# jam2.net
KiCad netlist of a schematic drawn in EAGLE
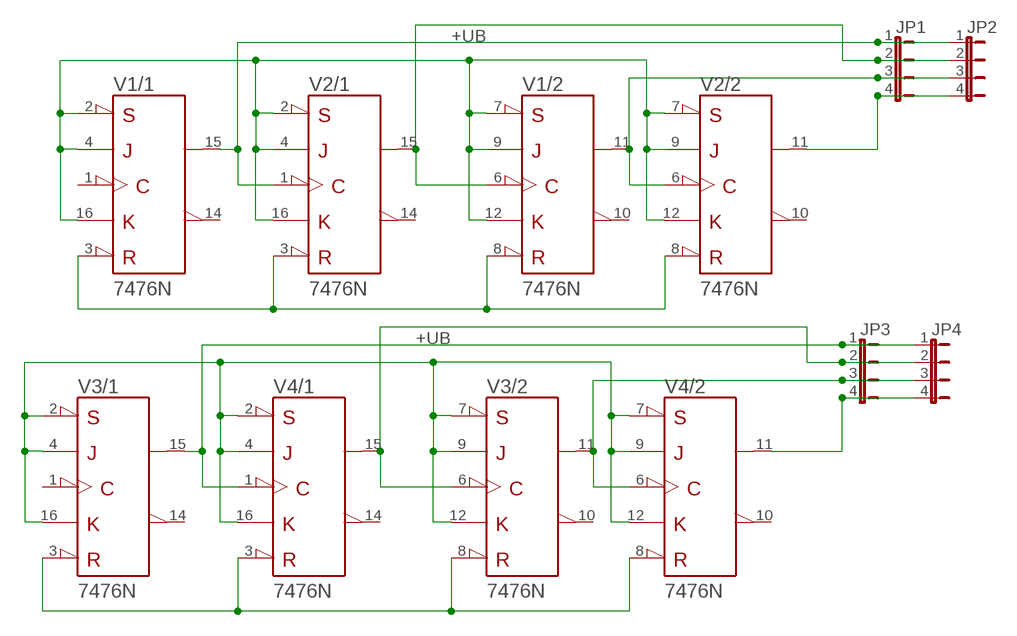
[diagram p0: schematic, sheet 1]

(export (version "E")
  (design (tool "Eeschema 10.0.6"))
  (components
    (comp (ref "JP1")
      (value "JP4E")
      (footprint "eagle-import:JP4")
      (libsource (lib "eagle-import") (part "JP4E"))
    )
    (comp (ref "JP2")
      (value "JP4E")
      (footprint "eagle-import:JP4")
      (libsource (lib "eagle-import") (part "JP4E"))
    )
    (comp (ref "JP3")
      (value "JP4E")
      (footprint "eagle-import:JP4")
      (libsource (lib "eagle-import") (part "JP4E"))
    )
    (comp (ref "JP4")
      (value "JP4E")
      (footprint "eagle-import:JP4")
      (libsource (lib "eagle-import") (part "JP4E"))
    )
    (comp (ref "V1")
      (value "7476N")
      (footprint "eagle-import:DIL16")
      (libsource (lib "eagle-import") (part "7476N"))
    )
    (comp (ref "V2")
      (value "7476N")
      (footprint "eagle-import:DIL16")
      (libsource (lib "eagle-import") (part "7476N"))
    )
    (comp (ref "V3")
      (value "7476N")
      (footprint "eagle-import:DIL16")
      (libsource (lib "eagle-import") (part "7476N"))
    )
    (comp (ref "V4")
      (value "7476N")
      (footprint "eagle-import:DIL16")
      (libsource (lib "eagle-import") (part "7476N"))
    )
  )
  (nets
    (net (code "1") (name "/+UB") (class "Default")
      (node (ref "V1") (pin "12") (pinfunction "K_12") (pintype "input"))
      (node (ref "V1") (pin "16") (pinfunction "K_16") (pintype "input"))
      (node (ref "V1") (pin "2") (pinfunction "~{PRE}_2") (pintype "input"))
      (node (ref "V1") (pin "4") (pinfunction "J_4") (pintype "input"))
      (node (ref "V1") (pin "7") (pinfunction "~{PRE}_7") (pintype "input"))
      (node (ref "V1") (pin "9") (pinfunction "J_9") (pintype "input"))
      (node (ref "V2") (pin "12") (pinfunction "K_12") (pintype "input"))
      (node (ref "V2") (pin "16") (pinfunction "K_16") (pintype "input"))
      (node (ref "V2") (pin "2") (pinfunction "~{PRE}_2") (pintype "input"))
      (node (ref "V2") (pin "4") (pinfunction "J_4") (pintype "input"))
      (node (ref "V2") (pin "7") (pinfunction "~{PRE}_7") (pintype "input"))
      (node (ref "V2") (pin "9") (pinfunction "J_9") (pintype "input"))
      (node (ref "V3") (pin "12") (pinfunction "K_12") (pintype "input"))
      (node (ref "V3") (pin "16") (pinfunction "K_16") (pintype "input"))
      (node (ref "V3") (pin "2") (pinfunction "~{PRE}_2") (pintype "input"))
      (node (ref "V3") (pin "4") (pinfunction "J_4") (pintype "input"))
      (node (ref "V3") (pin "7") (pinfunction "~{PRE}_7") (pintype "input"))
      (node (ref "V3") (pin "9") (pinfunction "J_9") (pintype "input"))
      (node (ref "V4") (pin "12") (pinfunction "K_12") (pintype "input"))
      (node (ref "V4") (pin "16") (pinfunction "K_16") (pintype "input"))
      (node (ref "V4") (pin "2") (pinfunction "~{PRE}_2") (pintype "input"))
      (node (ref "V4") (pin "4") (pinfunction "J_4") (pintype "input"))
      (node (ref "V4") (pin "7") (pinfunction "~{PRE}_7") (pintype "input"))
      (node (ref "V4") (pin "9") (pinfunction "J_9") (pintype "input"))
    )
    (net (code "2") (name "Net-(V1C-Q)") (class "Default")
      (node (ref "JP1") (pin "1") (pinfunction "1_1") (pintype "passive"))
      (node (ref "JP2") (pin "1") (pinfunction "1_1") (pintype "passive"))
      (node (ref "V1") (pin "15") (pinfunction "Q_15") (pintype "output"))
      (node (ref "V2") (pin "1") (pinfunction "CLK_1") (pintype "input"))
    )
    (net (code "3") (name "Net-(V1C-~{CLR})") (class "Default")
      (node (ref "V1") (pin "3") (pinfunction "~{CLR}_3") (pintype "input"))
      (node (ref "V1") (pin "8") (pinfunction "~{CLR}_8") (pintype "input"))
      (node (ref "V2") (pin "3") (pinfunction "~{CLR}_3") (pintype "input"))
      (node (ref "V2") (pin "8") (pinfunction "~{CLR}_8") (pintype "input"))
    )
    (net (code "4") (name "Net-(V1D-CLK)") (class "Default")
      (node (ref "JP1") (pin "2") (pinfunction "2_2") (pintype "passive"))
      (node (ref "JP2") (pin "2") (pinfunction "2_2") (pintype "passive"))
      (node (ref "V1") (pin "6") (pinfunction "CLK_6") (pintype "input"))
      (node (ref "V2") (pin "15") (pinfunction "Q_15") (pintype "output"))
    )
    (net (code "5") (name "Net-(V1D-Q)") (class "Default")
      (node (ref "JP1") (pin "3") (pinfunction "3_3") (pintype "passive"))
      (node (ref "JP2") (pin "3") (pinfunction "3_3") (pintype "passive"))
      (node (ref "V1") (pin "11") (pinfunction "Q_11") (pintype "output"))
      (node (ref "V2") (pin "6") (pinfunction "CLK_6") (pintype "input"))
    )
    (net (code "6") (name "Net-(V2D-Q)") (class "Default")
      (node (ref "JP1") (pin "4") (pinfunction "4_4") (pintype "passive"))
      (node (ref "JP2") (pin "4") (pinfunction "4_4") (pintype "passive"))
      (node (ref "V2") (pin "11") (pinfunction "Q_11") (pintype "output"))
    )
    (net (code "7") (name "Net-(V3C-Q)") (class "Default")
      (node (ref "JP3") (pin "1") (pinfunction "1_1") (pintype "passive"))
      (node (ref "JP4") (pin "1") (pinfunction "1_1") (pintype "passive"))
      (node (ref "V3") (pin "15") (pinfunction "Q_15") (pintype "output"))
      (node (ref "V4") (pin "1") (pinfunction "CLK_1") (pintype "input"))
    )
    (net (code "8") (name "Net-(V3C-~{CLR})") (class "Default")
      (node (ref "V3") (pin "3") (pinfunction "~{CLR}_3") (pintype "input"))
      (node (ref "V3") (pin "8") (pinfunction "~{CLR}_8") (pintype "input"))
      (node (ref "V4") (pin "3") (pinfunction "~{CLR}_3") (pintype "input"))
      (node (ref "V4") (pin "8") (pinfunction "~{CLR}_8") (pintype "input"))
    )
    (net (code "9") (name "Net-(V3D-CLK)") (class "Default")
      (node (ref "JP3") (pin "2") (pinfunction "2_2") (pintype "passive"))
      (node (ref "JP4") (pin "2") (pinfunction "2_2") (pintype "passive"))
      (node (ref "V3") (pin "6") (pinfunction "CLK_6") (pintype "input"))
      (node (ref "V4") (pin "15") (pinfunction "Q_15") (pintype "output"))
    )
    (net (code "10") (name "Net-(V3D-Q)") (class "Default")
      (node (ref "JP3") (pin "3") (pinfunction "3_3") (pintype "passive"))
      (node (ref "JP4") (pin "3") (pinfunction "3_3") (pintype "passive"))
      (node (ref "V3") (pin "11") (pinfunction "Q_11") (pintype "output"))
      (node (ref "V4") (pin "6") (pinfunction "CLK_6") (pintype "input"))
    )
    (net (code "11") (name "Net-(V4D-Q)") (class "Default")
      (node (ref "JP3") (pin "4") (pinfunction "4_4") (pintype "passive"))
      (node (ref "JP4") (pin "4") (pinfunction "4_4") (pintype "passive"))
      (node (ref "V4") (pin "11") (pinfunction "Q_11") (pintype "output"))
    )
    (net (code "12") (name "unconnected-(V1C-CLK-Pad1)") (class "Default")
      (node (ref "V1") (pin "1") (pinfunction "CLK_1") (pintype "input"))
    )
    (net (code "13") (name "unconnected-(V1C-~{Q}-Pad14)") (class "Default")
      (node (ref "V1") (pin "14") (pinfunction "~{Q}_14") (pintype "output"))
    )
    (net (code "14") (name "unconnected-(V1D-~{Q}-Pad10)") (class "Default")
      (node (ref "V1") (pin "10") (pinfunction "~{Q}_10") (pintype "output"))
    )
    (net (code "15") (name "unconnected-(V2C-~{Q}-Pad14)") (class "Default")
      (node (ref "V2") (pin "14") (pinfunction "~{Q}_14") (pintype "output"))
    )
    (net (code "16") (name "unconnected-(V2D-~{Q}-Pad10)") (class "Default")
      (node (ref "V2") (pin "10") (pinfunction "~{Q}_10") (pintype "output"))
    )
    (net (code "17") (name "unconnected-(V3C-CLK-Pad1)") (class "Default")
      (node (ref "V3") (pin "1") (pinfunction "CLK_1") (pintype "input"))
    )
    (net (code "18") (name "unconnected-(V3C-~{Q}-Pad14)") (class "Default")
      (node (ref "V3") (pin "14") (pinfunction "~{Q}_14") (pintype "output"))
    )
    (net (code "19") (name "unconnected-(V3D-~{Q}-Pad10)") (class "Default")
      (node (ref "V3") (pin "10") (pinfunction "~{Q}_10") (pintype "output"))
    )
    (net (code "20") (name "unconnected-(V4C-~{Q}-Pad14)") (class "Default")
      (node (ref "V4") (pin "14") (pinfunction "~{Q}_14") (pintype "output"))
    )
    (net (code "21") (name "unconnected-(V4D-~{Q}-Pad10)") (class "Default")
      (node (ref "V4") (pin "10") (pinfunction "~{Q}_10") (pintype "output"))
    )
  )
)
